# Sheet1.net
KiCad netlist of a schematic drawn in Altium Designer
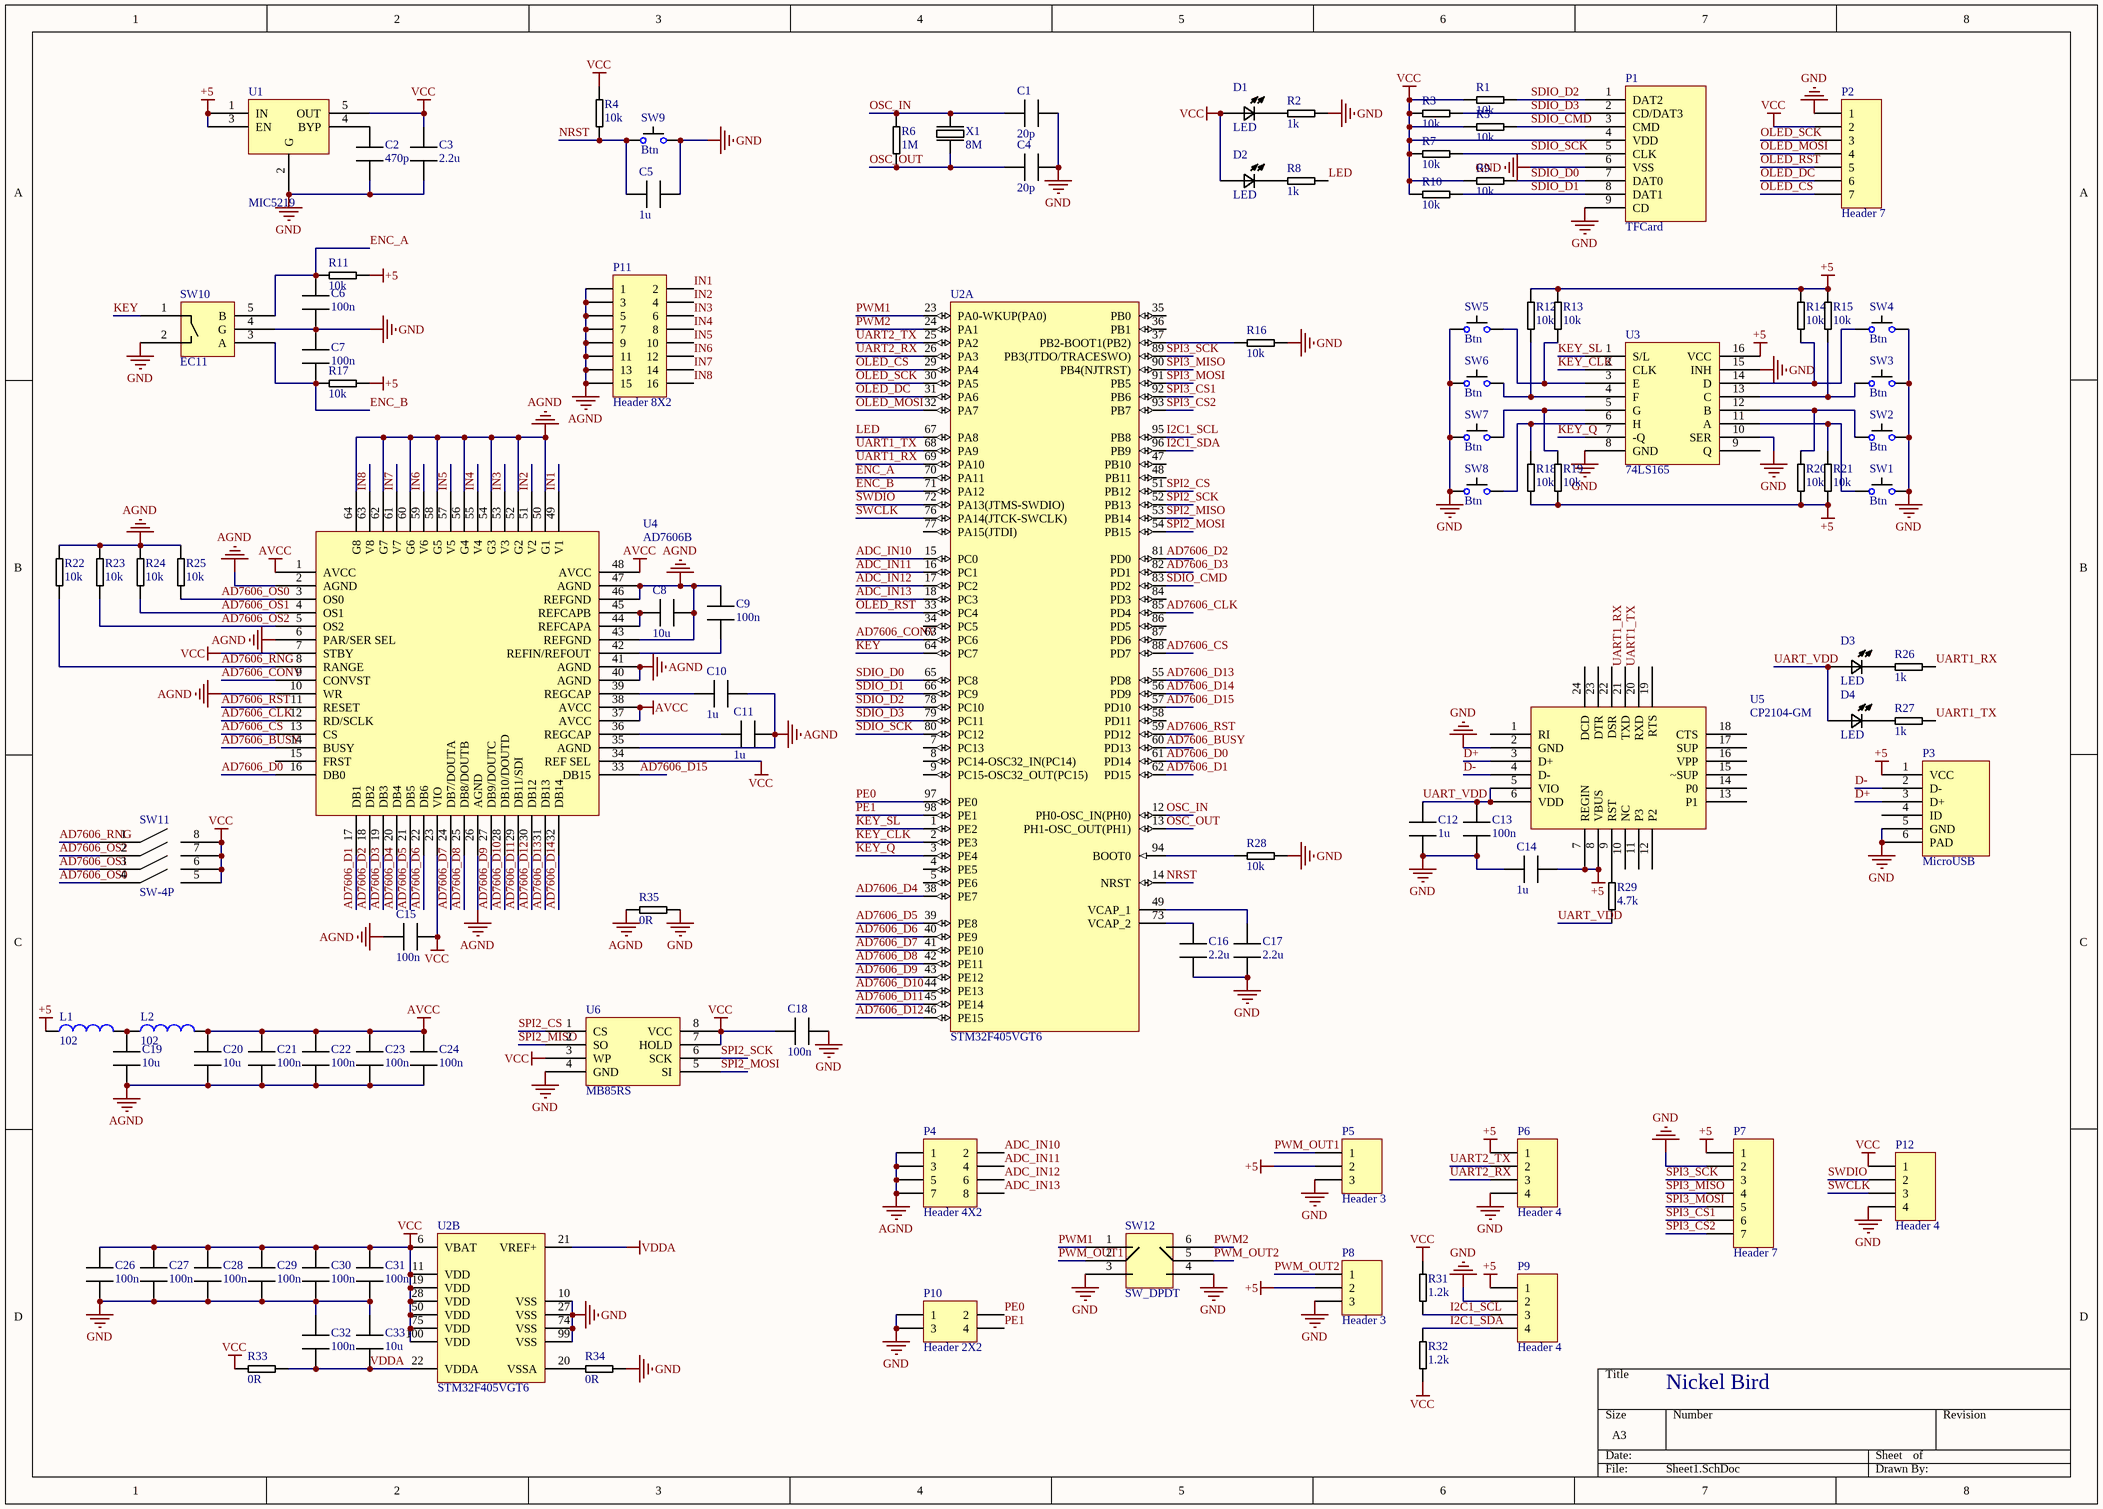
[diagram p0: Sheet1.SchDoc]

(export (version "E")
  (design (tool "Eeschema 10.0.6"))
  (components
    (comp (ref "C1") (value "20p") (footprint "0603") (libsource (lib "LibCfrpg") (part "Cap")))
    (comp (ref "C2") (value "470p") (footprint "0603") (libsource (lib "LibCfrpg") (part "Cap")))
    (comp (ref "C3") (value "2.2u") (footprint "0603") (libsource (lib "LibCfrpg") (part "Cap")))
    (comp (ref "C4") (value "20p") (footprint "0603") (libsource (lib "LibCfrpg") (part "Cap")))
    (comp (ref "C5") (value "1u") (footprint "0603") (libsource (lib "LibCfrpg") (part "Cap")))
    (comp (ref "C6") (value "100n") (footprint "0603") (libsource (lib "LibCfrpg") (part "Cap")))
    (comp (ref "C7") (value "100n") (footprint "0603") (libsource (lib "LibCfrpg") (part "Cap")))
    (comp (ref "C8") (value "10u") (footprint "0603") (libsource (lib "LibCfrpg") (part "Cap")))
    (comp (ref "C9") (value "100n") (footprint "0603") (libsource (lib "LibCfrpg") (part "Cap")))
    (comp (ref "C10") (value "1u") (footprint "0603") (libsource (lib "LibCfrpg") (part "Cap")))
    (comp (ref "C11") (value "1u") (footprint "0603") (libsource (lib "LibCfrpg") (part "Cap")))
    (comp (ref "C12") (value "1u") (footprint "0603") (libsource (lib "LibCfrpg") (part "Cap")))
    (comp (ref "C13") (value "100n") (footprint "0603") (libsource (lib "LibCfrpg") (part "Cap")))
    (comp (ref "C14") (value "1u") (footprint "0603") (libsource (lib "LibCfrpg") (part "Cap")))
    (comp (ref "C15") (value "100n") (footprint "0603") (libsource (lib "LibCfrpg") (part "Cap")))
    (comp (ref "C16") (value "2.2u") (footprint "0603") (libsource (lib "LibCfrpg") (part "Cap")))
    (comp (ref "C17") (value "2.2u") (footprint "0603") (libsource (lib "LibCfrpg") (part "Cap")))
    (comp (ref "C18") (value "100n") (footprint "0603") (libsource (lib "LibCfrpg") (part "Cap")))
    (comp (ref "C19") (value "10u") (footprint "0603") (libsource (lib "LibCfrpg") (part "Cap")))
    (comp (ref "C20") (value "10u") (footprint "0603") (libsource (lib "LibCfrpg") (part "Cap")))
    (comp (ref "C21") (value "100n") (footprint "0603") (libsource (lib "LibCfrpg") (part "Cap")))
    (comp (ref "C22") (value "100n") (footprint "0603") (libsource (lib "LibCfrpg") (part "Cap")))
    (comp (ref "C23") (value "100n") (footprint "0603") (libsource (lib "LibCfrpg") (part "Cap")))
    (comp (ref "C24") (value "100n") (footprint "0603") (libsource (lib "LibCfrpg") (part "Cap")))
    (comp (ref "C26") (value "100n") (footprint "0603") (libsource (lib "LibCfrpg") (part "Cap")))
    (comp (ref "C27") (value "100n") (footprint "0603") (libsource (lib "LibCfrpg") (part "Cap")))
    (comp (ref "C28") (value "100n") (footprint "0603") (libsource (lib "LibCfrpg") (part "Cap")))
    (comp (ref "C29") (value "100n") (footprint "0603") (libsource (lib "LibCfrpg") (part "Cap")))
    (comp (ref "C30") (value "100n") (footprint "0603") (libsource (lib "LibCfrpg") (part "Cap")))
    (comp (ref "C31") (value "100n") (footprint "0603") (libsource (lib "LibCfrpg") (part "Cap")))
    (comp (ref "C32") (value "100n") (footprint "0603") (libsource (lib "LibCfrpg") (part "Cap")))
    (comp (ref "C33") (value "10u") (footprint "0603") (libsource (lib "LibCfrpg") (part "Cap")))
    (comp (ref "D1") (value "LED") (footprint "0603-1") (libsource (lib "LibCfrpg") (part "LED")))
    (comp (ref "D2") (value "LED") (footprint "0603-1") (libsource (lib "LibCfrpg") (part "LED")))
    (comp (ref "D3") (value "LED") (footprint "0603-1") (libsource (lib "LibCfrpg") (part "LED")))
    (comp (ref "D4") (value "LED") (footprint "0603-1") (libsource (lib "LibCfrpg") (part "LED")))
    (comp (ref "L1")
      (value "102")
      (footprint "LibCfrpg:0603")
      (description "BLM18RK102SN1D")
      (libsource (lib "LibCfrpg") (part "Inductor"))
    )
    (comp (ref "L2")
      (value "102")
      (footprint "LibCfrpg:0603")
      (description "BLM18RK102SN1D")
      (libsource (lib "LibCfrpg") (part "Inductor"))
    )
    (comp (ref "P1") (value "TFCard") (footprint "TF Card") (libsource (lib "LibCfrpg") (part "TFCard")))
    (comp (ref "P2")
      (value "Header 7")
      (footprint "HDR1X7")
      (description "Header, 7-Pin")
      (fields (field (name "PUBLISHER") "Altium Limited"))
      (libsource (lib "Miscellaneous Connectors") (part "Header 7"))
    )
    (comp (ref "P3") (value "MicroUSB") (footprint "MicroUSB") (libsource (lib "LibCfrpg") (part "MicroUSB")))
    (comp (ref "P4")
      (value "Header 4X2")
      (footprint "HDR2X4")
      (description "Header, 4-Pin, Dual row")
      (fields (field (name "PUBLISHER") "Altium Limited"))
      (libsource (lib "Miscellaneous Connectors") (part "Header 4X2"))
    )
    (comp (ref "P5")
      (value "Header 3")
      (footprint "HDR1X3")
      (description "Header, 3-Pin")
      (fields (field (name "PUBLISHER") "Altium Limited"))
      (libsource (lib "Miscellaneous Connectors") (part "Header 3"))
    )
    (comp (ref "P6")
      (value "Header 4")
      (footprint "HDR1X4")
      (description "Header, 4-Pin")
      (fields (field (name "PUBLISHER") "Altium Limited"))
      (libsource (lib "Miscellaneous Connectors") (part "Header 4"))
    )
    (comp (ref "P7")
      (value "Header 7")
      (footprint "HDR1X7")
      (description "Header, 7-Pin")
      (fields (field (name "PUBLISHER") "Altium Limited"))
      (libsource (lib "Miscellaneous Connectors") (part "Header 7"))
    )
    (comp (ref "P8")
      (value "Header 3")
      (footprint "HDR1X3")
      (description "Header, 3-Pin")
      (fields (field (name "PUBLISHER") "Altium Limited"))
      (libsource (lib "Miscellaneous Connectors") (part "Header 3"))
    )
    (comp (ref "P9")
      (value "Header 4")
      (footprint "HDR1X4")
      (description "Header, 4-Pin")
      (fields (field (name "PUBLISHER") "Altium Limited"))
      (libsource (lib "Miscellaneous Connectors") (part "Header 4"))
    )
    (comp (ref "P10")
      (value "Header 2X2")
      (footprint "HDR2X2")
      (description "Header, 2-Pin, Dual row")
      (fields (field (name "PUBLISHER") "Altium Limited"))
      (libsource (lib "Miscellaneous Connectors") (part "Header 2X2"))
    )
    (comp (ref "P11")
      (value "Header 8X2")
      (footprint "HDR2X8")
      (description "Header, 8-Pin, Dual row")
      (fields (field (name "PUBLISHER") "Altium Limited"))
      (libsource (lib "Miscellaneous Connectors") (part "Header 8X2"))
    )
    (comp (ref "P12")
      (value "Header 4")
      (footprint "HDR1X4")
      (description "Header, 4-Pin")
      (fields (field (name "PUBLISHER") "Altium Limited"))
      (libsource (lib "Miscellaneous Connectors") (part "Header 4"))
    )
    (comp (ref "R1") (value "10k") (footprint "0603") (libsource (lib "LibCfrpg") (part "Res")))
    (comp (ref "R2") (value "1k") (footprint "0603") (libsource (lib "LibCfrpg") (part "Res")))
    (comp (ref "R3") (value "10k") (footprint "0603") (libsource (lib "LibCfrpg") (part "Res")))
    (comp (ref "R4") (value "10k") (footprint "0603") (libsource (lib "LibCfrpg") (part "Res")))
    (comp (ref "R5") (value "10k") (footprint "0603") (libsource (lib "LibCfrpg") (part "Res")))
    (comp (ref "R6") (value "1M") (footprint "0603") (libsource (lib "LibCfrpg") (part "Res")))
    (comp (ref "R7") (value "10k") (footprint "0603") (libsource (lib "LibCfrpg") (part "Res")))
    (comp (ref "R8") (value "1k") (footprint "0603") (libsource (lib "LibCfrpg") (part "Res")))
    (comp (ref "R9") (value "10k") (footprint "0603") (libsource (lib "LibCfrpg") (part "Res")))
    (comp (ref "R10") (value "10k") (footprint "0603") (libsource (lib "LibCfrpg") (part "Res")))
    (comp (ref "R11") (value "10k") (footprint "0603") (libsource (lib "LibCfrpg") (part "Res")))
    (comp (ref "R12") (value "10k") (footprint "0603") (libsource (lib "LibCfrpg") (part "Res")))
    (comp (ref "R13") (value "10k") (footprint "0603") (libsource (lib "LibCfrpg") (part "Res")))
    (comp (ref "R14") (value "10k") (footprint "0603") (libsource (lib "LibCfrpg") (part "Res")))
    (comp (ref "R15") (value "10k") (footprint "0603") (libsource (lib "LibCfrpg") (part "Res")))
    (comp (ref "R16") (value "10k") (footprint "0603") (libsource (lib "LibCfrpg") (part "Res")))
    (comp (ref "R17") (value "10k") (footprint "0603") (libsource (lib "LibCfrpg") (part "Res")))
    (comp (ref "R18") (value "10k") (footprint "0603") (libsource (lib "LibCfrpg") (part "Res")))
    (comp (ref "R19") (value "10k") (footprint "0603") (libsource (lib "LibCfrpg") (part "Res")))
    (comp (ref "R20") (value "10k") (footprint "0603") (libsource (lib "LibCfrpg") (part "Res")))
    (comp (ref "R21") (value "10k") (footprint "0603") (libsource (lib "LibCfrpg") (part "Res")))
    (comp (ref "R22") (value "10k") (footprint "0603") (libsource (lib "LibCfrpg") (part "Res")))
    (comp (ref "R23") (value "10k") (footprint "0603") (libsource (lib "LibCfrpg") (part "Res")))
    (comp (ref "R24") (value "10k") (footprint "0603") (libsource (lib "LibCfrpg") (part "Res")))
    (comp (ref "R25") (value "10k") (footprint "0603") (libsource (lib "LibCfrpg") (part "Res")))
    (comp (ref "R26") (value "1k") (footprint "0603") (libsource (lib "LibCfrpg") (part "Res")))
    (comp (ref "R27") (value "1k") (footprint "0603") (libsource (lib "LibCfrpg") (part "Res")))
    (comp (ref "R28") (value "10k") (footprint "0603") (libsource (lib "LibCfrpg") (part "Res")))
    (comp (ref "R29") (value "4.7k") (footprint "0603") (libsource (lib "LibCfrpg") (part "Res")))
    (comp (ref "R31") (value "1.2k") (footprint "0603") (libsource (lib "LibCfrpg") (part "Res")))
    (comp (ref "R32") (value "1.2k") (footprint "0603") (libsource (lib "LibCfrpg") (part "Res")))
    (comp (ref "R33") (value "0R") (footprint "0603") (libsource (lib "LibCfrpg") (part "Res")))
    (comp (ref "R34") (value "0R") (footprint "0603") (libsource (lib "LibCfrpg") (part "Res")))
    (comp (ref "R35") (value "0R") (footprint "0603") (libsource (lib "LibCfrpg") (part "Res")))
    (comp (ref "SW1") (value "Btn") (footprint "BTN3*3") (libsource (lib "LibCfrpg") (part "Btn")))
    (comp (ref "SW2") (value "Btn") (footprint "BTN3*3") (libsource (lib "LibCfrpg") (part "Btn")))
    (comp (ref "SW3") (value "Btn") (footprint "BTN3*3") (libsource (lib "LibCfrpg") (part "Btn")))
    (comp (ref "SW4") (value "Btn") (footprint "BTN3*3") (libsource (lib "LibCfrpg") (part "Btn")))
    (comp (ref "SW5") (value "Btn") (footprint "BTN3*3") (libsource (lib "LibCfrpg") (part "Btn")))
    (comp (ref "SW6") (value "Btn") (footprint "BTN3*3") (libsource (lib "LibCfrpg") (part "Btn")))
    (comp (ref "SW7") (value "Btn") (footprint "BTN3*3") (libsource (lib "LibCfrpg") (part "Btn")))
    (comp (ref "SW8") (value "Btn") (footprint "BTN3*3") (libsource (lib "LibCfrpg") (part "Btn")))
    (comp (ref "SW9") (value "Btn") (footprint "BTN3*3") (libsource (lib "LibCfrpg") (part "Btn")))
    (comp (ref "SW10") (value "EC11") (footprint "EC11") (libsource (lib "LibCfrpg") (part "EC11")))
    (comp (ref "SW11") (value "SW-4P") (footprint "SW-1.27-4P") (libsource (lib "LibCfrpg") (part "SW-4P")))
    (comp (ref "SW12") (value "SW_DPDT") (footprint "DPDT7mm") (libsource (lib "LibCfrpg") (part "SW_DPDT")))
    (comp (ref "U1") (value "MIC5219") (footprint "SOT23-5") (libsource (lib "LibCfrpg") (part "MIC5219")))
    (comp (ref "U2")
      (value "STM32F405VGT6")
      (footprint "STM-LQFP100_N")
      (fields (field (name "MANUFACTURER") "STMicroelectronics"))
      (libsource (lib "STMicroelectronics STM32 F4") (part "STM32F405VGT6"))
    )
    (comp (ref "U3") (value "74LS165") (footprint "SOP16") (libsource (lib "LibCfrpg") (part "74LS165")))
    (comp (ref "U4") (value "AD7606B") (footprint "LQFP-64") (libsource (lib "LibCfrpg") (part "AD7606B")))
    (comp (ref "U5")
      (value "CP2104-GM")
      (footprint "QFN-24-Pad")
      (libsource (lib "LibCfrpg") (part "CP2104-GM"))
    )
    (comp (ref "U6") (value "MB85RS") (footprint "SOP8") (libsource (lib "LibCfrpg") (part "MB85RS")))
    (comp (ref "X1") (value "8M") (footprint "49SMD") (libsource (lib "LibCfrpg") (part "XTAL")))
  )
  (nets
    (net (code "1") (name "+5") (class "Default")
      (node (ref "C14") (pin "2") (pintype "passive"))
      (node (ref "L1") (pin "1") (pinfunction "1_1") (pintype "passive"))
      (node (ref "P3") (pin "1") (pinfunction "VCC_1") (pintype "passive"))
      (node (ref "P5") (pin "2") (pinfunction "2_2") (pintype "passive"))
      (node (ref "P6") (pin "1") (pinfunction "1_1") (pintype "passive"))
      (node (ref "P7") (pin "1") (pinfunction "1_1") (pintype "passive"))
      (node (ref "P8") (pin "2") (pinfunction "2_2") (pintype "passive"))
      (node (ref "P9") (pin "1") (pinfunction "1_1") (pintype "passive"))
      (node (ref "R11") (pin "2") (pintype "passive"))
      (node (ref "R12") (pin "2") (pintype "passive"))
      (node (ref "R13") (pin "2") (pintype "passive"))
      (node (ref "R14") (pin "2") (pintype "passive"))
      (node (ref "R15") (pin "2") (pintype "passive"))
      (node (ref "R17") (pin "2") (pintype "passive"))
      (node (ref "R18") (pin "1") (pintype "passive"))
      (node (ref "R19") (pin "1") (pintype "passive"))
      (node (ref "R20") (pin "1") (pintype "passive"))
      (node (ref "R21") (pin "1") (pintype "passive"))
      (node (ref "U1") (pin "1") (pinfunction "IN_1") (pintype "passive"))
      (node (ref "U1") (pin "3") (pinfunction "EN_3") (pintype "passive"))
      (node (ref "U3") (pin "16") (pinfunction "VCC_16") (pintype "passive"))
      (node (ref "U5") (pin "7") (pinfunction "REGIN_7") (pintype "passive"))
      (node (ref "U5") (pin "8") (pinfunction "VBUS_8") (pintype "passive"))
    )
    (net (code "2") (name "/AD7606_BUSY") (class "Default")
      (node (ref "U2") (pin "60") (pinfunction "PD13_60") (pintype "bidirectional"))
      (node (ref "U4") (pin "14") (pinfunction "BUSY_14") (pintype "passive"))
    )
    (net (code "3") (name "/AD7606_CLK") (class "Default")
      (node (ref "U2") (pin "85") (pinfunction "PD4_85") (pintype "bidirectional"))
      (node (ref "U4") (pin "12") (pinfunction "RD/SCLK_12") (pintype "passive"))
    )
    (net (code "4") (name "/AD7606_CONV") (class "Default")
      (node (ref "U2") (pin "63") (pinfunction "PC6_63") (pintype "bidirectional"))
      (node (ref "U4") (pin "9") (pinfunction "CONVST_9") (pintype "passive"))
    )
    (net (code "5") (name "/AD7606_CS") (class "Default")
      (node (ref "U2") (pin "88") (pinfunction "PD7_88") (pintype "bidirectional"))
      (node (ref "U4") (pin "13") (pinfunction "CS_13") (pintype "passive"))
    )
    (net (code "6") (name "/AD7606_D0") (class "Default")
      (node (ref "U2") (pin "61") (pinfunction "PD14_61") (pintype "bidirectional"))
      (node (ref "U4") (pin "16") (pinfunction "DB0_16") (pintype "passive"))
    )
    (net (code "7") (name "/AD7606_D1") (class "Default")
      (node (ref "U2") (pin "62") (pinfunction "PD15_62") (pintype "bidirectional"))
      (node (ref "U4") (pin "17") (pinfunction "DB1_17") (pintype "passive"))
    )
    (net (code "8") (name "/AD7606_D2") (class "Default")
      (node (ref "U2") (pin "81") (pinfunction "PD0_81") (pintype "bidirectional"))
      (node (ref "U4") (pin "18") (pinfunction "DB2_18") (pintype "passive"))
    )
    (net (code "9") (name "/AD7606_D3") (class "Default")
      (node (ref "U2") (pin "82") (pinfunction "PD1_82") (pintype "bidirectional"))
      (node (ref "U4") (pin "19") (pinfunction "DB3_19") (pintype "passive"))
    )
    (net (code "10") (name "/AD7606_D4") (class "Default")
      (node (ref "U2") (pin "38") (pinfunction "PE7_38") (pintype "bidirectional"))
      (node (ref "U4") (pin "20") (pinfunction "DB4_20") (pintype "passive"))
    )
    (net (code "11") (name "/AD7606_D5") (class "Default")
      (node (ref "U2") (pin "39") (pinfunction "PE8_39") (pintype "bidirectional"))
      (node (ref "U4") (pin "21") (pinfunction "DB5_21") (pintype "passive"))
    )
    (net (code "12") (name "/AD7606_D6") (class "Default")
      (node (ref "U2") (pin "40") (pinfunction "PE9_40") (pintype "bidirectional"))
      (node (ref "U4") (pin "22") (pinfunction "DB6_22") (pintype "passive"))
    )
    (net (code "13") (name "/AD7606_D7") (class "Default")
      (node (ref "U2") (pin "41") (pinfunction "PE10_41") (pintype "bidirectional"))
      (node (ref "U4") (pin "24") (pinfunction "DB7/DOUTA_24") (pintype "passive"))
    )
    (net (code "14") (name "/AD7606_D8") (class "Default")
      (node (ref "U2") (pin "42") (pinfunction "PE11_42") (pintype "bidirectional"))
      (node (ref "U4") (pin "25") (pinfunction "DB8/DOUTB_25") (pintype "passive"))
    )
    (net (code "15") (name "/AD7606_D9") (class "Default")
      (node (ref "U2") (pin "43") (pinfunction "PE12_43") (pintype "bidirectional"))
      (node (ref "U4") (pin "27") (pinfunction "DB9/DOUTC_27") (pintype "passive"))
    )
    (net (code "16") (name "/AD7606_D10") (class "Default")
      (node (ref "U2") (pin "44") (pinfunction "PE13_44") (pintype "bidirectional"))
      (node (ref "U4") (pin "28") (pinfunction "DB10/DOUTD_28") (pintype "passive"))
    )
    (net (code "17") (name "/AD7606_D11") (class "Default")
      (node (ref "U2") (pin "45") (pinfunction "PE14_45") (pintype "bidirectional"))
      (node (ref "U4") (pin "29") (pinfunction "DB11/SDI_29") (pintype "passive"))
    )
    (net (code "18") (name "/AD7606_D12") (class "Default")
      (node (ref "U2") (pin "46") (pinfunction "PE15_46") (pintype "bidirectional"))
      (node (ref "U4") (pin "30") (pinfunction "DB12_30") (pintype "passive"))
    )
    (net (code "19") (name "/AD7606_D13") (class "Default")
      (node (ref "U2") (pin "55") (pinfunction "PD8_55") (pintype "bidirectional"))
      (node (ref "U4") (pin "31") (pinfunction "DB13_31") (pintype "passive"))
    )
    (net (code "20") (name "/AD7606_D14") (class "Default")
      (node (ref "U2") (pin "56") (pinfunction "PD9_56") (pintype "bidirectional"))
      (node (ref "U4") (pin "32") (pinfunction "DB14_32") (pintype "passive"))
    )
    (net (code "21") (name "/AD7606_D15") (class "Default")
      (node (ref "U2") (pin "57") (pinfunction "PD10_57") (pintype "bidirectional"))
      (node (ref "U4") (pin "33") (pinfunction "DB15_33") (pintype "passive"))
    )
    (net (code "22") (name "/AD7606_OS0") (class "Default")
      (node (ref "R25") (pin "1") (pintype "passive"))
      (node (ref "SW11") (pin "4") (pinfunction "4_4") (pintype "passive"))
      (node (ref "U4") (pin "3") (pinfunction "OS0_3") (pintype "passive"))
    )
    (net (code "23") (name "/AD7606_OS1") (class "Default")
      (node (ref "R24") (pin "1") (pintype "passive"))
      (node (ref "SW11") (pin "3") (pinfunction "3_3") (pintype "passive"))
      (node (ref "U4") (pin "4") (pinfunction "OS1_4") (pintype "passive"))
    )
    (net (code "24") (name "/AD7606_OS2") (class "Default")
      (node (ref "R23") (pin "1") (pintype "passive"))
      (node (ref "SW11") (pin "2") (pinfunction "2_2") (pintype "passive"))
      (node (ref "U4") (pin "5") (pinfunction "OS2_5") (pintype "passive"))
    )
    (net (code "25") (name "/AD7606_RNG") (class "Default")
      (node (ref "R22") (pin "1") (pintype "passive"))
      (node (ref "SW11") (pin "1") (pinfunction "1_1") (pintype "passive"))
      (node (ref "U4") (pin "8") (pinfunction "RANGE_8") (pintype "passive"))
    )
    (net (code "26") (name "/AD7606_RST") (class "Default")
      (node (ref "U2") (pin "59") (pinfunction "PD12_59") (pintype "bidirectional"))
      (node (ref "U4") (pin "11") (pinfunction "RESET_11") (pintype "passive"))
    )
    (net (code "27") (name "/ADC_IN10") (class "Default")
      (node (ref "P4") (pin "2") (pinfunction "2_2") (pintype "passive"))
      (node (ref "U2") (pin "15") (pinfunction "PC0_15") (pintype "bidirectional"))
    )
    (net (code "28") (name "/ADC_IN11") (class "Default")
      (node (ref "P4") (pin "4") (pinfunction "4_4") (pintype "passive"))
      (node (ref "U2") (pin "16") (pinfunction "PC1_16") (pintype "bidirectional"))
    )
    (net (code "29") (name "/ADC_IN12") (class "Default")
      (node (ref "P4") (pin "6") (pinfunction "6_6") (pintype "passive"))
      (node (ref "U2") (pin "17") (pinfunction "PC2_17") (pintype "bidirectional"))
    )
    (net (code "30") (name "/ADC_IN13") (class "Default")
      (node (ref "P4") (pin "8") (pinfunction "8_8") (pintype "passive"))
      (node (ref "U2") (pin "18") (pinfunction "PC3_18") (pintype "bidirectional"))
    )
    (net (code "31") (name "/D+") (class "Default")
      (node (ref "P3") (pin "3") (pinfunction "D+_3") (pintype "passive"))
      (node (ref "U5") (pin "3") (pinfunction "D+_3") (pintype "passive"))
    )
    (net (code "32") (name "/D-") (class "Default")
      (node (ref "P3") (pin "2") (pinfunction "D-_2") (pintype "passive"))
      (node (ref "U5") (pin "4") (pinfunction "D-_4") (pintype "passive"))
    )
    (net (code "33") (name "/ENC_A") (class "Default")
      (node (ref "C6") (pin "2") (pintype "passive"))
      (node (ref "R11") (pin "1") (pintype "passive"))
      (node (ref "SW10") (pin "5") (pinfunction "B_5") (pintype "passive"))
      (node (ref "U2") (pin "70") (pinfunction "PA11_70") (pintype "bidirectional"))
    )
    (net (code "34") (name "/ENC_B") (class "Default")
      (node (ref "C7") (pin "1") (pintype "passive"))
      (node (ref "R17") (pin "1") (pintype "passive"))
      (node (ref "SW10") (pin "3") (pinfunction "A_3") (pintype "passive"))
      (node (ref "U2") (pin "71") (pinfunction "PA12_71") (pintype "bidirectional"))
    )
    (net (code "35") (name "/I2C1_SCL") (class "Default")
      (node (ref "P9") (pin "3") (pinfunction "3_3") (pintype "passive"))
      (node (ref "R31") (pin "1") (pintype "passive"))
      (node (ref "U2") (pin "95") (pinfunction "PB8_95") (pintype "bidirectional"))
    )
    (net (code "36") (name "/I2C1_SDA") (class "Default")
      (node (ref "P9") (pin "4") (pinfunction "4_4") (pintype "passive"))
      (node (ref "R32") (pin "2") (pintype "passive"))
      (node (ref "U2") (pin "96") (pinfunction "PB9_96") (pintype "bidirectional"))
    )
    (net (code "37") (name "/IN1") (class "Default")
      (node (ref "P11") (pin "2") (pinfunction "2_2") (pintype "passive"))
      (node (ref "U4") (pin "49") (pinfunction "V1_49") (pintype "passive"))
    )
    (net (code "38") (name "/IN2") (class "Default")
      (node (ref "P11") (pin "4") (pinfunction "4_4") (pintype "passive"))
      (node (ref "U4") (pin "51") (pinfunction "V2_51") (pintype "passive"))
    )
    (net (code "39") (name "/IN3") (class "Default")
      (node (ref "P11") (pin "6") (pinfunction "6_6") (pintype "passive"))
      (node (ref "U4") (pin "53") (pinfunction "V3_53") (pintype "passive"))
    )
    (net (code "40") (name "/IN4") (class "Default")
      (node (ref "P11") (pin "8") (pinfunction "8_8") (pintype "passive"))
      (node (ref "U4") (pin "55") (pinfunction "V4_55") (pintype "passive"))
    )
    (net (code "41") (name "/IN5") (class "Default")
      (node (ref "P11") (pin "10") (pinfunction "10_10") (pintype "passive"))
      (node (ref "U4") (pin "57") (pinfunction "V5_57") (pintype "passive"))
    )
    (net (code "42") (name "/IN6") (class "Default")
      (node (ref "P11") (pin "12") (pinfunction "12_12") (pintype "passive"))
      (node (ref "U4") (pin "59") (pinfunction "V6_59") (pintype "passive"))
    )
    (net (code "43") (name "/IN7") (class "Default")
      (node (ref "P11") (pin "14") (pinfunction "14_14") (pintype "passive"))
      (node (ref "U4") (pin "61") (pinfunction "V7_61") (pintype "passive"))
    )
    (net (code "44") (name "/IN8") (class "Default")
      (node (ref "P11") (pin "16") (pinfunction "16_16") (pintype "passive"))
      (node (ref "U4") (pin "63") (pinfunction "V8_63") (pintype "passive"))
    )
    (net (code "45") (name "/KEY") (class "Default")
      (node (ref "SW10") (pin "1") (pinfunction "K_1") (pintype "passive"))
      (node (ref "U2") (pin "64") (pinfunction "PC7_64") (pintype "bidirectional"))
    )
    (net (code "46") (name "/KEY_CLK") (class "Default")
      (node (ref "U2") (pin "2") (pinfunction "PE3_2") (pintype "bidirectional"))
      (node (ref "U3") (pin "2") (pinfunction "CLK_2") (pintype "passive"))
    )
    (net (code "47") (name "/KEY_Q") (class "Default")
      (node (ref "U2") (pin "3") (pinfunction "PE4_3") (pintype "bidirectional"))
      (node (ref "U3") (pin "7") (pinfunction "-Q_7") (pintype "passive"))
    )
    (net (code "48") (name "/KEY_SL") (class "Default")
      (node (ref "U2") (pin "1") (pinfunction "PE2_1") (pintype "bidirectional"))
      (node (ref "U3") (pin "1") (pinfunction "S/L_1") (pintype "passive"))
    )
    (net (code "49") (name "/LED") (class "Default")
      (node (ref "R8") (pin "2") (pintype "passive"))
      (node (ref "U2") (pin "67") (pinfunction "PA8_67") (pintype "bidirectional"))
    )
    (net (code "50") (name "/NRST") (class "Default")
      (node (ref "C5") (pin "1") (pintype "passive"))
      (node (ref "R4") (pin "1") (pintype "passive"))
      (node (ref "SW9") (pin "1") (pintype "passive"))
      (node (ref "U2") (pin "14") (pinfunction "NRST_14") (pintype "bidirectional"))
    )
    (net (code "51") (name "/OLED_CS") (class "Default")
      (node (ref "P2") (pin "7") (pinfunction "7_7") (pintype "passive"))
      (node (ref "U2") (pin "29") (pinfunction "PA4_29") (pintype "bidirectional"))
    )
    (net (code "52") (name "/OLED_DC") (class "Default")
      (node (ref "P2") (pin "6") (pinfunction "6_6") (pintype "passive"))
      (node (ref "U2") (pin "31") (pinfunction "PA6_31") (pintype "bidirectional"))
    )
    (net (code "53") (name "/OLED_MOSI") (class "Default")
      (node (ref "P2") (pin "4") (pinfunction "4_4") (pintype "passive"))
      (node (ref "U2") (pin "32") (pinfunction "PA7_32") (pintype "bidirectional"))
    )
    (net (code "54") (name "/OLED_RST") (class "Default")
      (node (ref "P2") (pin "5") (pinfunction "5_5") (pintype "passive"))
      (node (ref "U2") (pin "33") (pinfunction "PC4_33") (pintype "bidirectional"))
    )
    (net (code "55") (name "/OLED_SCK") (class "Default")
      (node (ref "P2") (pin "3") (pinfunction "3_3") (pintype "passive"))
      (node (ref "U2") (pin "30") (pinfunction "PA5_30") (pintype "bidirectional"))
    )
    (net (code "56") (name "/OSC_IN") (class "Default")
      (node (ref "C1") (pin "1") (pintype "passive"))
      (node (ref "R6") (pin "2") (pintype "passive"))
      (node (ref "U2") (pin "12") (pinfunction "PH0-OSC_IN(PH0)_12") (pintype "bidirectional"))
      (node (ref "X1") (pin "2") (pintype "passive"))
    )
    (net (code "57") (name "/OSC_OUT") (class "Default")
      (node (ref "C4") (pin "1") (pintype "passive"))
      (node (ref "R6") (pin "1") (pintype "passive"))
      (node (ref "U2") (pin "13") (pinfunction "PH1-OSC_OUT(PH1)_13") (pintype "bidirectional"))
      (node (ref "X1") (pin "1") (pintype "passive"))
    )
    (net (code "58") (name "/PE0") (class "Default")
      (node (ref "P10") (pin "2") (pinfunction "2_2") (pintype "passive"))
      (node (ref "U2") (pin "97") (pinfunction "PE0_97") (pintype "bidirectional"))
    )
    (net (code "59") (name "/PE1") (class "Default")
      (node (ref "P10") (pin "4") (pinfunction "4_4") (pintype "passive"))
      (node (ref "U2") (pin "98") (pinfunction "PE1_98") (pintype "bidirectional"))
    )
    (net (code "60") (name "/PWM1") (class "Default")
      (node (ref "SW12") (pin "1") (pintype "passive"))
      (node (ref "U2") (pin "23") (pinfunction "PA0-WKUP(PA0)_23") (pintype "bidirectional"))
    )
    (net (code "61") (name "/PWM2") (class "Default")
      (node (ref "SW12") (pin "6") (pinfunction "6_6") (pintype "passive"))
      (node (ref "U2") (pin "24") (pinfunction "PA1_24") (pintype "bidirectional"))
    )
    (net (code "62") (name "/PWM_OUT1") (class "Default")
      (node (ref "P5") (pin "1") (pinfunction "1_1") (pintype "passive"))
      (node (ref "SW12") (pin "2") (pinfunction "2_2") (pintype "passive"))
    )
    (net (code "63") (name "/PWM_OUT2") (class "Default")
      (node (ref "P8") (pin "1") (pinfunction "1_1") (pintype "passive"))
      (node (ref "SW12") (pin "5") (pinfunction "5_5") (pintype "passive"))
    )
    (net (code "64") (name "/SDIO_CMD") (class "Default")
      (node (ref "P1") (pin "3") (pinfunction "CMD_3") (pintype "passive"))
      (node (ref "R5") (pin "2") (pintype "passive"))
      (node (ref "U2") (pin "83") (pinfunction "PD2_83") (pintype "bidirectional"))
    )
    (net (code "65") (name "/SDIO_D0") (class "Default")
      (node (ref "P1") (pin "7") (pinfunction "DAT0_7") (pintype "passive"))
      (node (ref "R9") (pin "2") (pintype "passive"))
      (node (ref "U2") (pin "65") (pinfunction "PC8_65") (pintype "bidirectional"))
    )
    (net (code "66") (name "/SDIO_D1") (class "Default")
      (node (ref "P1") (pin "8") (pinfunction "DAT1_8") (pintype "passive"))
      (node (ref "R10") (pin "2") (pintype "passive"))
      (node (ref "U2") (pin "66") (pinfunction "PC9_66") (pintype "bidirectional"))
    )
    (net (code "67") (name "/SDIO_D2") (class "Default")
      (node (ref "P1") (pin "1") (pinfunction "DAT2_1") (pintype "passive"))
      (node (ref "R1") (pin "2") (pintype "passive"))
      (node (ref "U2") (pin "78") (pinfunction "PC10_78") (pintype "bidirectional"))
    )
    (net (code "68") (name "/SDIO_D3") (class "Default")
      (node (ref "P1") (pin "2") (pinfunction "CD/DAT3_2") (pintype "passive"))
      (node (ref "R3") (pin "2") (pintype "passive"))
      (node (ref "U2") (pin "79") (pinfunction "PC11_79") (pintype "bidirectional"))
    )
    (net (code "69") (name "/SDIO_SCK") (class "Default")
      (node (ref "P1") (pin "5") (pinfunction "CLK_5") (pintype "passive"))
      (node (ref "R7") (pin "2") (pintype "passive"))
      (node (ref "U2") (pin "80") (pinfunction "PC12_80") (pintype "bidirectional"))
    )
    (net (code "70") (name "/SPI2_CS") (class "Default")
      (node (ref "U2") (pin "51") (pinfunction "PB12_51") (pintype "bidirectional"))
      (node (ref "U6") (pin "1") (pinfunction "CS_1") (pintype "passive"))
    )
    (net (code "71") (name "/SPI2_MISO") (class "Default")
      (node (ref "U2") (pin "53") (pinfunction "PB14_53") (pintype "bidirectional"))
      (node (ref "U6") (pin "2") (pinfunction "SO_2") (pintype "passive"))
    )
    (net (code "72") (name "/SPI2_MOSI") (class "Default")
      (node (ref "U2") (pin "54") (pinfunction "PB15_54") (pintype "bidirectional"))
      (node (ref "U6") (pin "5") (pinfunction "SI_5") (pintype "passive"))
    )
    (net (code "73") (name "/SPI2_SCK") (class "Default")
      (node (ref "U2") (pin "52") (pinfunction "PB13_52") (pintype "bidirectional"))
      (node (ref "U6") (pin "6") (pinfunction "SCK_6") (pintype "passive"))
    )
    (net (code "74") (name "/SPI3_CS1") (class "Default")
      (node (ref "P7") (pin "6") (pinfunction "6_6") (pintype "passive"))
      (node (ref "U2") (pin "92") (pinfunction "PB6_92") (pintype "bidirectional"))
    )
    (net (code "75") (name "/SPI3_CS2") (class "Default")
      (node (ref "P7") (pin "7") (pinfunction "7_7") (pintype "passive"))
      (node (ref "U2") (pin "93") (pinfunction "PB7_93") (pintype "bidirectional"))
    )
    (net (code "76") (name "/SPI3_MISO") (class "Default")
      (node (ref "P7") (pin "4") (pinfunction "4_4") (pintype "passive"))
      (node (ref "U2") (pin "90") (pinfunction "PB4(NJTRST)_90") (pintype "bidirectional"))
    )
    (net (code "77") (name "/SPI3_MOSI") (class "Default")
      (node (ref "P7") (pin "5") (pinfunction "5_5") (pintype "passive"))
      (node (ref "U2") (pin "91") (pinfunction "PB5_91") (pintype "bidirectional"))
    )
    (net (code "78") (name "/SPI3_SCK") (class "Default")
      (node (ref "P7") (pin "3") (pinfunction "3_3") (pintype "passive"))
      (node (ref "U2") (pin "89") (pinfunction "PB3(JTDO/TRACESWO)_89") (pintype "bidirectional"))
    )
    (net (code "79") (name "/SWCLK") (class "Default")
      (node (ref "P12") (pin "3") (pinfunction "3_3") (pintype "passive"))
      (node (ref "U2") (pin "76") (pinfunction "PA14(JTCK-SWCLK)_76") (pintype "bidirectional"))
    )
    (net (code "80") (name "/SWDIO") (class "Default")
      (node (ref "P12") (pin "2") (pinfunction "2_2") (pintype "passive"))
      (node (ref "U2") (pin "72") (pinfunction "PA13(JTMS-SWDIO)_72") (pintype "bidirectional"))
    )
    (net (code "81") (name "/UART1_RX") (class "Default")
      (node (ref "R26") (pin "2") (pintype "passive"))
      (node (ref "U2") (pin "69") (pinfunction "PA10_69") (pintype "bidirectional"))
      (node (ref "U5") (pin "21") (pinfunction "TXD_21") (pintype "passive"))
    )
    (net (code "82") (name "/UART1_TX") (class "Default")
      (node (ref "R27") (pin "2") (pintype "passive"))
      (node (ref "U2") (pin "68") (pinfunction "PA9_68") (pintype "bidirectional"))
      (node (ref "U5") (pin "20") (pinfunction "RXD_20") (pintype "passive"))
    )
    (net (code "83") (name "/UART2_RX") (class "Default")
      (node (ref "P6") (pin "3") (pinfunction "3_3") (pintype "passive"))
      (node (ref "U2") (pin "26") (pinfunction "PA3_26") (pintype "bidirectional"))
    )
    (net (code "84") (name "/UART2_TX") (class "Default")
      (node (ref "P6") (pin "2") (pinfunction "2_2") (pintype "passive"))
      (node (ref "U2") (pin "25") (pinfunction "PA2_25") (pintype "bidirectional"))
    )
    (net (code "85") (name "/UART_VDD") (class "Default")
      (node (ref "C12") (pin "2") (pintype "passive"))
      (node (ref "C13") (pin "2") (pintype "passive"))
      (node (ref "D3") (pin "1") (pintype "passive"))
      (node (ref "D4") (pin "1") (pintype "passive"))
      (node (ref "R29") (pin "1") (pintype "passive"))
      (node (ref "U5") (pin "5") (pinfunction "VIO_5") (pintype "passive"))
      (node (ref "U5") (pin "6") (pinfunction "VDD_6") (pintype "passive"))
    )
    (net (code "86") (name "AGND") (class "Default")
      (node (ref "C10") (pin "2") (pintype "passive"))
      (node (ref "C11") (pin "2") (pintype "passive"))
      (node (ref "C15") (pin "1") (pintype "passive"))
      (node (ref "C19") (pin "1") (pintype "passive"))
      (node (ref "C20") (pin "1") (pintype "passive"))
      (node (ref "C21") (pin "1") (pintype "passive"))
      (node (ref "C22") (pin "1") (pintype "passive"))
      (node (ref "C23") (pin "1") (pintype "passive"))
      (node (ref "C24") (pin "1") (pintype "passive"))
      (node (ref "C8") (pin "2") (pintype "passive"))
      (node (ref "C9") (pin "2") (pintype "passive"))
      (node (ref "P11") (pin "1") (pinfunction "1_1") (pintype "passive"))
      (node (ref "P11") (pin "11") (pinfunction "11_11") (pintype "passive"))
      (node (ref "P11") (pin "13") (pinfunction "13_13") (pintype "passive"))
      (node (ref "P11") (pin "15") (pinfunction "15_15") (pintype "passive"))
      (node (ref "P11") (pin "3") (pinfunction "3_3") (pintype "passive"))
      (node (ref "P11") (pin "5") (pinfunction "5_5") (pintype "passive"))
      (node (ref "P11") (pin "7") (pinfunction "7_7") (pintype "passive"))
      (node (ref "P11") (pin "9") (pinfunction "9_9") (pintype "passive"))
      (node (ref "P4") (pin "1") (pinfunction "1_1") (pintype "passive"))
      (node (ref "P4") (pin "3") (pinfunction "3_3") (pintype "passive"))
      (node (ref "P4") (pin "5") (pinfunction "5_5") (pintype "passive"))
      (node (ref "P4") (pin "7") (pinfunction "7_7") (pintype "passive"))
      (node (ref "R22") (pin "2") (pintype "passive"))
      (node (ref "R23") (pin "2") (pintype "passive"))
      (node (ref "R24") (pin "2") (pintype "passive"))
      (node (ref "R25") (pin "2") (pintype "passive"))
      (node (ref "R35") (pin "1") (pintype "passive"))
      (node (ref "U4") (pin "10") (pinfunction "WR_10") (pintype "passive"))
      (node (ref "U4") (pin "2") (pinfunction "AGND_2") (pintype "passive"))
      (node (ref "U4") (pin "26") (pinfunction "AGND_26") (pintype "passive"))
      (node (ref "U4") (pin "35") (pinfunction "AGND_35") (pintype "passive"))
      (node (ref "U4") (pin "40") (pinfunction "AGND_40") (pintype "passive"))
      (node (ref "U4") (pin "41") (pinfunction "AGND_41") (pintype "passive"))
      (node (ref "U4") (pin "43") (pinfunction "REFGND_43") (pintype "passive"))
      (node (ref "U4") (pin "46") (pinfunction "REFGND_46") (pintype "passive"))
      (node (ref "U4") (pin "47") (pinfunction "AGND_47") (pintype "passive"))
      (node (ref "U4") (pin "50") (pinfunction "G1_50") (pintype "passive"))
      (node (ref "U4") (pin "52") (pinfunction "G2_52") (pintype "passive"))
      (node (ref "U4") (pin "54") (pinfunction "G3_54") (pintype "passive"))
      (node (ref "U4") (pin "56") (pinfunction "G4_56") (pintype "passive"))
      (node (ref "U4") (pin "58") (pinfunction "G5_58") (pintype "passive"))
      (node (ref "U4") (pin "6") (pinfunction "PAR/SER_SEL_6") (pintype "passive"))
      (node (ref "U4") (pin "60") (pinfunction "G6_60") (pintype "passive"))
      (node (ref "U4") (pin "62") (pinfunction "G7_62") (pintype "passive"))
      (node (ref "U4") (pin "64") (pinfunction "G8_64") (pintype "passive"))
    )
    (net (code "87") (name "AVCC") (class "Default")
      (node (ref "C20") (pin "2") (pintype "passive"))
      (node (ref "C21") (pin "2") (pintype "passive"))
      (node (ref "C22") (pin "2") (pintype "passive"))
      (node (ref "C23") (pin "2") (pintype "passive"))
      (node (ref "C24") (pin "2") (pintype "passive"))
      (node (ref "L2") (pin "2") (pinfunction "2_2") (pintype "passive"))
      (node (ref "U4") (pin "1") (pinfunction "AVCC_1") (pintype "passive"))
      (node (ref "U4") (pin "37") (pinfunction "AVCC_37") (pintype "passive"))
      (node (ref "U4") (pin "38") (pinfunction "AVCC_38") (pintype "passive"))
      (node (ref "U4") (pin "48") (pinfunction "AVCC_48") (pintype "passive"))
    )
    (net (code "88") (name "GND") (class "Default")
      (node (ref "C1") (pin "2") (pintype "passive"))
      (node (ref "C12") (pin "1") (pintype "passive"))
      (node (ref "C13") (pin "1") (pintype "passive"))
      (node (ref "C14") (pin "1") (pintype "passive"))
      (node (ref "C16") (pin "1") (pintype "passive"))
      (node (ref "C17") (pin "1") (pintype "passive"))
      (node (ref "C18") (pin "2") (pintype "passive"))
      (node (ref "C2") (pin "1") (pintype "passive"))
      (node (ref "C26") (pin "1") (pintype "passive"))
      (node (ref "C27") (pin "1") (pintype "passive"))
      (node (ref "C28") (pin "1") (pintype "passive"))
      (node (ref "C29") (pin "1") (pintype "passive"))
      (node (ref "C3") (pin "1") (pintype "passive"))
      (node (ref "C30") (pin "1") (pintype "passive"))
      (node (ref "C31") (pin "1") (pintype "passive"))
      (node (ref "C32") (pin "2") (pintype "passive"))
      (node (ref "C33") (pin "2") (pintype "passive"))
      (node (ref "C4") (pin "2") (pintype "passive"))
      (node (ref "C5") (pin "2") (pintype "passive"))
      (node (ref "C6") (pin "1") (pintype "passive"))
      (node (ref "C7") (pin "2") (pintype "passive"))
      (node (ref "P1") (pin "6") (pinfunction "VSS_6") (pintype "passive"))
      (node (ref "P1") (pin "9") (pinfunction "CD_9") (pintype "passive"))
      (node (ref "P10") (pin "1") (pinfunction "1_1") (pintype "passive"))
      (node (ref "P10") (pin "3") (pinfunction "3_3") (pintype "passive"))
      (node (ref "P12") (pin "4") (pinfunction "4_4") (pintype "passive"))
      (node (ref "P2") (pin "1") (pinfunction "1_1") (pintype "passive"))
      (node (ref "P3") (pin "5") (pinfunction "GND_5") (pintype "passive"))
      (node (ref "P3") (pin "6") (pinfunction "PAD_6") (pintype "passive"))
      (node (ref "P5") (pin "3") (pinfunction "3_3") (pintype "passive"))
      (node (ref "P6") (pin "4") (pinfunction "4_4") (pintype "passive"))
      (node (ref "P7") (pin "2") (pinfunction "2_2") (pintype "passive"))
      (node (ref "P8") (pin "3") (pinfunction "3_3") (pintype "passive"))
      (node (ref "P9") (pin "2") (pinfunction "2_2") (pintype "passive"))
      (node (ref "R16") (pin "2") (pintype "passive"))
      (node (ref "R2") (pin "2") (pintype "passive"))
      (node (ref "R28") (pin "2") (pintype "passive"))
      (node (ref "R34") (pin "2") (pintype "passive"))
      (node (ref "R35") (pin "2") (pintype "passive"))
      (node (ref "SW1") (pin "2") (pintype "passive"))
      (node (ref "SW10") (pin "2") (pinfunction "A_2") (pintype "passive"))
      (node (ref "SW10") (pin "4") (pinfunction "G_4") (pintype "passive"))
      (node (ref "SW12") (pin "3") (pinfunction "3_3") (pintype "passive"))
      (node (ref "SW12") (pin "4") (pinfunction "4_4") (pintype "passive"))
      (node (ref "SW2") (pin "2") (pintype "passive"))
      (node (ref "SW3") (pin "2") (pintype "passive"))
      (node (ref "SW4") (pin "2") (pintype "passive"))
      (node (ref "SW5") (pin "1") (pintype "passive"))
      (node (ref "SW6") (pin "1") (pintype "passive"))
      (node (ref "SW7") (pin "1") (pintype "passive"))
      (node (ref "SW8") (pin "1") (pintype "passive"))
      (node (ref "SW9") (pin "2") (pintype "passive"))
      (node (ref "U1") (pin "2") (pinfunction "G_2") (pintype "passive"))
      (node (ref "U2") (pin "10") (pinfunction "VSS_10") (pintype "power_in"))
      (node (ref "U2") (pin "27") (pinfunction "VSS_27") (pintype "power_in"))
      (node (ref "U2") (pin "74") (pinfunction "VSS_74") (pintype "power_in"))
      (node (ref "U2") (pin "99") (pinfunction "VSS_99") (pintype "power_in"))
      (node (ref "U3") (pin "10") (pinfunction "SER_10") (pintype "passive"))
      (node (ref "U3") (pin "15") (pinfunction "INH_15") (pintype "passive"))
      (node (ref "U3") (pin "8") (pinfunction "GND_8") (pintype "passive"))
      (node (ref "U5") (pin "2") (pinfunction "GND_2") (pintype "passive"))
      (node (ref "U6") (pin "4") (pinfunction "GND_4") (pintype "passive"))
    )
    (net (code "89") (name "Net-(C10-Pad1)") (class "Default")
      (node (ref "C10") (pin "1") (pintype "passive"))
      (node (ref "U4") (pin "39") (pinfunction "REGCAP_39") (pintype "passive"))
    )
    (net (code "90") (name "Net-(C11-Pad1)") (class "Default")
      (node (ref "C11") (pin "1") (pintype "passive"))
      (node (ref "U4") (pin "36") (pinfunction "REGCAP_36") (pintype "passive"))
    )
    (net (code "91") (name "Net-(C19-Pad2)") (class "Default")
      (node (ref "C19") (pin "2") (pintype "passive"))
      (node (ref "L1") (pin "2") (pinfunction "2_2") (pintype "passive"))
      (node (ref "L2") (pin "1") (pinfunction "1_1") (pintype "passive"))
    )
    (net (code "92") (name "Net-(D1-Pad2)") (class "Default")
      (node (ref "D1") (pin "2") (pintype "passive"))
      (node (ref "R2") (pin "1") (pintype "passive"))
    )
    (net (code "93") (name "Net-(D2-Pad2)") (class "Default")
      (node (ref "D2") (pin "2") (pintype "passive"))
      (node (ref "R8") (pin "1") (pintype "passive"))
    )
    (net (code "94") (name "Net-(D3-Pad2)") (class "Default")
      (node (ref "D3") (pin "2") (pintype "passive"))
      (node (ref "R26") (pin "1") (pintype "passive"))
    )
    (net (code "95") (name "Net-(D4-Pad2)") (class "Default")
      (node (ref "D4") (pin "2") (pintype "passive"))
      (node (ref "R27") (pin "1") (pintype "passive"))
    )
    (net (code "96") (name "Net-(U1-BYP)") (class "Default")
      (node (ref "C2") (pin "2") (pintype "passive"))
      (node (ref "U1") (pin "4") (pinfunction "BYP_4") (pintype "passive"))
    )
    (net (code "97") (name "Net-(U2A-BOOT0)") (class "Default")
      (node (ref "R28") (pin "1") (pintype "passive"))
      (node (ref "U2") (pin "94") (pinfunction "BOOT0_94") (pintype "input"))
    )
    (net (code "98") (name "Net-(U2A-PB2-BOOT1(PB2))") (class "Default")
      (node (ref "R16") (pin "1") (pintype "passive"))
      (node (ref "U2") (pin "37") (pinfunction "PB2-BOOT1(PB2)_37") (pintype "bidirectional"))
    )
    (net (code "99") (name "Net-(U2A-VCAP_1)") (class "Default")
      (node (ref "C17") (pin "2") (pintype "passive"))
      (node (ref "U2") (pin "49") (pinfunction "VCAP_1_49") (pintype "power_in"))
    )
    (net (code "100") (name "Net-(U2A-VCAP_2)") (class "Default")
      (node (ref "C16") (pin "2") (pintype "passive"))
      (node (ref "U2") (pin "73") (pinfunction "VCAP_2_73") (pintype "power_in"))
    )
    (net (code "101") (name "Net-(U2B-VSSA)") (class "Default")
      (node (ref "R34") (pin "1") (pintype "passive"))
      (node (ref "U2") (pin "20") (pinfunction "VSSA_20") (pintype "power_in"))
    )
    (net (code "102") (name "Net-(U3-A)") (class "Default")
      (node (ref "R21") (pin "2") (pintype "passive"))
      (node (ref "SW1") (pin "1") (pintype "passive"))
      (node (ref "U3") (pin "11") (pinfunction "A_11") (pintype "passive"))
    )
    (net (code "103") (name "Net-(U3-B)") (class "Default")
      (node (ref "R20") (pin "2") (pintype "passive"))
      (node (ref "SW2") (pin "1") (pintype "passive"))
      (node (ref "U3") (pin "12") (pinfunction "B_12") (pintype "passive"))
    )
    (net (code "104") (name "Net-(U3-C)") (class "Default")
      (node (ref "R15") (pin "1") (pintype "passive"))
      (node (ref "SW3") (pin "1") (pintype "passive"))
      (node (ref "U3") (pin "13") (pinfunction "C_13") (pintype "passive"))
    )
    (net (code "105") (name "Net-(U3-D)") (class "Default")
      (node (ref "R14") (pin "1") (pintype "passive"))
      (node (ref "SW4") (pin "1") (pintype "passive"))
      (node (ref "U3") (pin "14") (pinfunction "D_14") (pintype "passive"))
    )
    (net (code "106") (name "Net-(U3-E)") (class "Default")
      (node (ref "R13") (pin "1") (pintype "passive"))
      (node (ref "SW5") (pin "2") (pintype "passive"))
      (node (ref "U3") (pin "3") (pinfunction "E_3") (pintype "passive"))
    )
    (net (code "107") (name "Net-(U3-F)") (class "Default")
      (node (ref "R12") (pin "1") (pintype "passive"))
      (node (ref "SW6") (pin "2") (pintype "passive"))
      (node (ref "U3") (pin "4") (pinfunction "F_4") (pintype "passive"))
    )
    (net (code "108") (name "Net-(U3-G)") (class "Default")
      (node (ref "R19") (pin "2") (pintype "passive"))
      (node (ref "SW7") (pin "2") (pintype "passive"))
      (node (ref "U3") (pin "5") (pinfunction "G_5") (pintype "passive"))
    )
    (net (code "109") (name "Net-(U3-H)") (class "Default")
      (node (ref "R18") (pin "2") (pintype "passive"))
      (node (ref "SW8") (pin "2") (pintype "passive"))
      (node (ref "U3") (pin "6") (pinfunction "H_6") (pintype "passive"))
    )
    (net (code "110") (name "Net-(U4-REFCAPA)") (class "Default")
      (node (ref "C8") (pin "1") (pintype "passive"))
      (node (ref "U4") (pin "44") (pinfunction "REFCAPA_44") (pintype "passive"))
      (node (ref "U4") (pin "45") (pinfunction "REFCAPB_45") (pintype "passive"))
    )
    (net (code "111") (name "Net-(U4-REFIN{slash}REFOUT)") (class "Default")
      (node (ref "C9") (pin "1") (pintype "passive"))
      (node (ref "U4") (pin "42") (pinfunction "REFIN/REFOUT_42") (pintype "passive"))
    )
    (net (code "112") (name "Net-(U5-RST)") (class "Default")
      (node (ref "R29") (pin "2") (pintype "passive"))
      (node (ref "U5") (pin "9") (pinfunction "RST_9") (pintype "passive"))
    )
    (net (code "113") (name "VCC") (class "Default")
      (node (ref "C15") (pin "2") (pintype "passive"))
      (node (ref "C18") (pin "1") (pintype "passive"))
      (node (ref "C26") (pin "2") (pintype "passive"))
      (node (ref "C27") (pin "2") (pintype "passive"))
      (node (ref "C28") (pin "2") (pintype "passive"))
      (node (ref "C29") (pin "2") (pintype "passive"))
      (node (ref "C3") (pin "2") (pintype "passive"))
      (node (ref "C30") (pin "2") (pintype "passive"))
      (node (ref "C31") (pin "2") (pintype "passive"))
      (node (ref "D1") (pin "1") (pintype "passive"))
      (node (ref "D2") (pin "1") (pintype "passive"))
      (node (ref "P1") (pin "4") (pinfunction "VDD_4") (pintype "passive"))
      (node (ref "P12") (pin "1") (pinfunction "1_1") (pintype "passive"))
      (node (ref "P2") (pin "2") (pinfunction "2_2") (pintype "passive"))
      (node (ref "R1") (pin "1") (pintype "passive"))
      (node (ref "R10") (pin "1") (pintype "passive"))
      (node (ref "R3") (pin "1") (pintype "passive"))
      (node (ref "R31") (pin "2") (pintype "passive"))
      (node (ref "R32") (pin "1") (pintype "passive"))
      (node (ref "R33") (pin "1") (pintype "passive"))
      (node (ref "R4") (pin "2") (pintype "passive"))
      (node (ref "R5") (pin "1") (pintype "passive"))
      (node (ref "R7") (pin "1") (pintype "passive"))
      (node (ref "R9") (pin "1") (pintype "passive"))
      (node (ref "SW11") (pin "5") (pinfunction "5_5") (pintype "passive"))
      (node (ref "SW11") (pin "6") (pinfunction "6_6") (pintype "passive"))
      (node (ref "SW11") (pin "7") (pinfunction "7_7") (pintype "passive"))
      (node (ref "SW11") (pin "8") (pinfunction "8_8") (pintype "passive"))
      (node (ref "U1") (pin "5") (pinfunction "OUT_5") (pintype "passive"))
      (node (ref "U2") (pin "100") (pinfunction "VDD_100") (pintype "power_in"))
      (node (ref "U2") (pin "11") (pinfunction "VDD_11") (pintype "power_in"))
      (node (ref "U2") (pin "19") (pinfunction "VDD_19") (pintype "power_in"))
      (node (ref "U2") (pin "28") (pinfunction "VDD_28") (pintype "power_in"))
      (node (ref "U2") (pin "50") (pinfunction "VDD_50") (pintype "power_in"))
      (node (ref "U2") (pin "6") (pinfunction "VBAT_6") (pintype "power_in"))
      (node (ref "U2") (pin "75") (pinfunction "VDD_75") (pintype "power_in"))
      (node (ref "U4") (pin "23") (pinfunction "VIO_23") (pintype "passive"))
      (node (ref "U4") (pin "34") (pinfunction "REF_SEL_34") (pintype "passive"))
      (node (ref "U4") (pin "7") (pinfunction "STBY_7") (pintype "passive"))
      (node (ref "U6") (pin "3") (pinfunction "WP_3") (pintype "passive"))
      (node (ref "U6") (pin "7") (pinfunction "HOLD_7") (pintype "passive"))
      (node (ref "U6") (pin "8") (pinfunction "VCC_8") (pintype "passive"))
    )
    (net (code "114") (name "VDDA") (class "Default")
      (node (ref "C32") (pin "1") (pintype "passive"))
      (node (ref "C33") (pin "1") (pintype "passive"))
      (node (ref "R33") (pin "2") (pintype "passive"))
      (node (ref "U2") (pin "21") (pinfunction "VREF+_21") (pintype "power_in"))
      (node (ref "U2") (pin "22") (pinfunction "VDDA_22") (pintype "power_in"))
    )
    (net (code "115") (name "unconnected-(P3-ID-Pad4)") (class "Default")
      (node (ref "P3") (pin "4") (pinfunction "ID_4") (pintype "passive"))
    )
    (net (code "116") (name "unconnected-(U2A-PA15(JTDI)-Pad77)") (class "Default")
      (node (ref "U2") (pin "77") (pinfunction "PA15(JTDI)_77") (pintype "bidirectional"))
    )
    (net (code "117") (name "unconnected-(U2A-PB0-Pad35)") (class "Default")
      (node (ref "U2") (pin "35") (pinfunction "PB0_35") (pintype "bidirectional"))
    )
    (net (code "118") (name "unconnected-(U2A-PB1-Pad36)") (class "Default")
      (node (ref "U2") (pin "36") (pinfunction "PB1_36") (pintype "bidirectional"))
    )
    (net (code "119") (name "unconnected-(U2A-PB10-Pad47)") (class "Default")
      (node (ref "U2") (pin "47") (pinfunction "PB10_47") (pintype "bidirectional"))
    )
    (net (code "120") (name "unconnected-(U2A-PB11-Pad48)") (class "Default")
      (node (ref "U2") (pin "48") (pinfunction "PB11_48") (pintype "bidirectional"))
    )
    (net (code "121") (name "unconnected-(U2A-PC5-Pad34)") (class "Default")
      (node (ref "U2") (pin "34") (pinfunction "PC5_34") (pintype "bidirectional"))
    )
    (net (code "122") (name "unconnected-(U2A-PC13-Pad7)") (class "Default")
      (node (ref "U2") (pin "7") (pinfunction "PC13_7") (pintype "bidirectional"))
    )
    (net (code "123") (name "unconnected-(U2A-PC14-OSC32_IN(PC14)-Pad8)") (class "Default")
      (node (ref "U2") (pin "8") (pinfunction "PC14-OSC32_IN(PC14)_8") (pintype "bidirectional"))
    )
    (net (code "124") (name "unconnected-(U2A-PC15-OSC32_OUT(PC15)-Pad9)") (class "Default")
      (node (ref "U2") (pin "9") (pinfunction "PC15-OSC32_OUT(PC15)_9") (pintype "bidirectional"))
    )
    (net (code "125") (name "unconnected-(U2A-PD3-Pad84)") (class "Default")
      (node (ref "U2") (pin "84") (pinfunction "PD3_84") (pintype "bidirectional"))
    )
    (net (code "126") (name "unconnected-(U2A-PD5-Pad86)") (class "Default")
      (node (ref "U2") (pin "86") (pinfunction "PD5_86") (pintype "bidirectional"))
    )
    (net (code "127") (name "unconnected-(U2A-PD6-Pad87)") (class "Default")
      (node (ref "U2") (pin "87") (pinfunction "PD6_87") (pintype "bidirectional"))
    )
    (net (code "128") (name "unconnected-(U2A-PD11-Pad58)") (class "Default")
      (node (ref "U2") (pin "58") (pinfunction "PD11_58") (pintype "bidirectional"))
    )
    (net (code "129") (name "unconnected-(U2A-PE5-Pad4)") (class "Default")
      (node (ref "U2") (pin "4") (pinfunction "PE5_4") (pintype "bidirectional"))
    )
    (net (code "130") (name "unconnected-(U2A-PE6-Pad5)") (class "Default")
      (node (ref "U2") (pin "5") (pinfunction "PE6_5") (pintype "bidirectional"))
    )
    (net (code "131") (name "unconnected-(U3-Q-Pad9)") (class "Default")
      (node (ref "U3") (pin "9") (pinfunction "Q_9") (pintype "passive"))
    )
    (net (code "132") (name "unconnected-(U4-FRST-Pad15)") (class "Default")
      (node (ref "U4") (pin "15") (pinfunction "FRST_15") (pintype "passive"))
    )
    (net (code "133") (name "unconnected-(U5-CTS-Pad18)") (class "Default")
      (node (ref "U5") (pin "18") (pinfunction "CTS_18") (pintype "passive"))
    )
    (net (code "134") (name "unconnected-(U5-DCD-Pad24)") (class "Default")
      (node (ref "U5") (pin "24") (pinfunction "DCD_24") (pintype "passive"))
    )
    (net (code "135") (name "unconnected-(U5-DSR-Pad22)") (class "Default")
      (node (ref "U5") (pin "22") (pinfunction "DSR_22") (pintype "passive"))
    )
    (net (code "136") (name "unconnected-(U5-DTR-Pad23)") (class "Default")
      (node (ref "U5") (pin "23") (pinfunction "DTR_23") (pintype "passive"))
    )
    (net (code "137") (name "unconnected-(U5-NC-Pad10)") (class "Default")
      (node (ref "U5") (pin "10") (pinfunction "NC_10") (pintype "passive"))
    )
    (net (code "138") (name "unconnected-(U5-P0-Pad14)") (class "Default")
      (node (ref "U5") (pin "14") (pinfunction "P0_14") (pintype "passive"))
    )
    (net (code "139") (name "unconnected-(U5-P1-Pad13)") (class "Default")
      (node (ref "U5") (pin "13") (pinfunction "P1_13") (pintype "passive"))
    )
    (net (code "140") (name "unconnected-(U5-P2-Pad12)") (class "Default")
      (node (ref "U5") (pin "12") (pinfunction "P2_12") (pintype "passive"))
    )
    (net (code "141") (name "unconnected-(U5-P3-Pad11)") (class "Default")
      (node (ref "U5") (pin "11") (pinfunction "P3_11") (pintype "passive"))
    )
    (net (code "142") (name "unconnected-(U5-RI-Pad1)") (class "Default")
      (node (ref "U5") (pin "1") (pinfunction "RI_1") (pintype "passive"))
    )
    (net (code "143") (name "unconnected-(U5-RTS-Pad19)") (class "Default")
      (node (ref "U5") (pin "19") (pinfunction "RTS_19") (pintype "passive"))
    )
    (net (code "144") (name "unconnected-(U5-SUP-Pad17)") (class "Default")
      (node (ref "U5") (pin "17") (pinfunction "SUP_17") (pintype "passive"))
    )
    (net (code "145") (name "unconnected-(U5-VPP-Pad16)") (class "Default")
      (node (ref "U5") (pin "16") (pinfunction "VPP_16") (pintype "passive"))
    )
    (net (code "146") (name "unconnected-(U5-~SUP-Pad15)") (class "Default")
      (node (ref "U5") (pin "15") (pinfunction "~SUP_15") (pintype "passive"))
    )
  )
)
